# Sheet4.net
KiCad netlist of a schematic drawn in Altium Designer
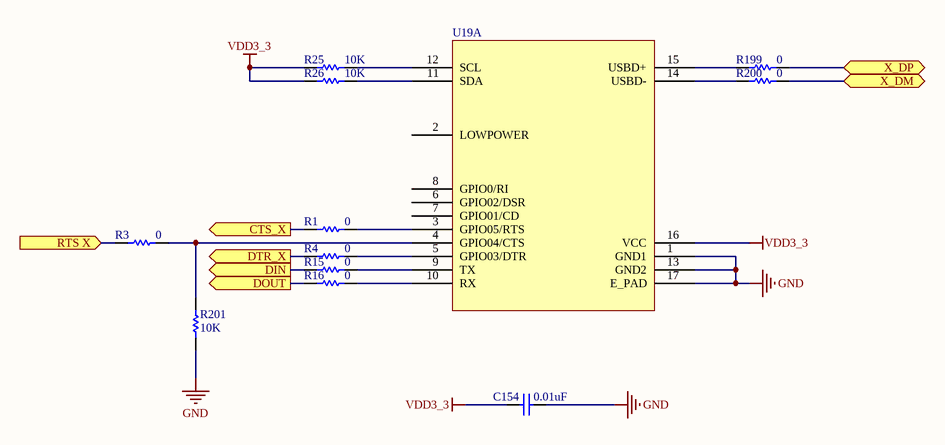
[diagram p0: Sheet4.SchDoc]

(export (version "E")
  (design (tool "Eeschema 10.0.6"))
  (components
    (comp (ref "C154")
      (value "0.01uF")
      (footprint "CAPC1005X35N")
      (description "Capacitor")
      (fields (field (name "Comment") "Cap") (field (name "PUBLISHER") "Altium Limited"))
      (libsource (lib "Miscellaneous Devices") (part "Cap"))
    )
    (comp (ref "R1")
      (value "0")
      (footprint "RESC1005X35N")
      (description "Resistor")
      (fields (field (name "Comment") "Res1") (field (name "PUBLISHER") "Altium Limited"))
      (libsource (lib "Miscellaneous Devices") (part "Res1"))
    )
    (comp (ref "R3")
      (value "0")
      (footprint "RESC1005X35N")
      (description "Resistor")
      (fields (field (name "Comment") "Res1") (field (name "PUBLISHER") "Altium Limited"))
      (libsource (lib "Miscellaneous Devices") (part "Res1"))
    )
    (comp (ref "R4")
      (value "0")
      (footprint "RESC1005X35N")
      (description "Resistor")
      (fields (field (name "Comment") "Res1") (field (name "PUBLISHER") "Altium Limited"))
      (libsource (lib "Miscellaneous Devices") (part "Res1"))
    )
    (comp (ref "R15")
      (value "0")
      (footprint "RESC1005X35N")
      (description "Resistor")
      (fields (field (name "Comment") "Res1") (field (name "PUBLISHER") "Altium Limited"))
      (libsource (lib "Miscellaneous Devices") (part "Res1"))
    )
    (comp (ref "R16")
      (value "0")
      (footprint "RESC1005X35N")
      (description "Resistor")
      (fields (field (name "Comment") "Res1") (field (name "PUBLISHER") "Altium Limited"))
      (libsource (lib "Miscellaneous Devices") (part "Res1"))
    )
    (comp (ref "R25")
      (value "10K")
      (footprint "RESC1005X35N")
      (description "Resistor")
      (fields (field (name "Comment") "Res1") (field (name "PUBLISHER") "Altium Limited"))
      (libsource (lib "Miscellaneous Devices") (part "Res1"))
    )
    (comp (ref "R26")
      (value "10K")
      (footprint "RESC1005X35N")
      (description "Resistor")
      (fields (field (name "Comment") "Res1") (field (name "PUBLISHER") "Altium Limited"))
      (libsource (lib "Miscellaneous Devices") (part "Res1"))
    )
    (comp (ref "R199")
      (value "0")
      (footprint "RESC1005X35N")
      (description "Resistor")
      (fields (field (name "Comment") "Res1") (field (name "PUBLISHER") "Altium Limited"))
      (libsource (lib "Miscellaneous Devices") (part "Res1"))
    )
    (comp (ref "R200")
      (value "0")
      (footprint "RESC1005X35N")
      (description "Resistor")
      (fields (field (name "Comment") "Res1") (field (name "PUBLISHER") "Altium Limited"))
      (libsource (lib "Miscellaneous Devices") (part "Res1"))
    )
    (comp (ref "R201")
      (value "10K")
      (footprint "RESC1005X35N")
      (description "Resistor")
      (fields (field (name "Comment") "Res1") (field (name "PUBLISHER") "Altium Limited"))
      (libsource (lib "Miscellaneous Devices") (part "Res1"))
    )
    (comp (ref "U19")
      (value "~")
      (footprint "QFN50P300X300X90-17N")
      (libsource (lib "Components - 07.03.22 - 14.02") (part "XR21V1410"))
    )
  )
  (nets
    (net (code "1") (name "/CTS_X") (class "Default")
      (node (ref "R1") (pin "1") (pinfunction "1_1") (pintype "passive"))
    )
    (net (code "2") (name "/DIN") (class "Default")
      (node (ref "R15") (pin "1") (pinfunction "1_1") (pintype "passive"))
    )
    (net (code "3") (name "/DOUT") (class "Default")
      (node (ref "R16") (pin "1") (pinfunction "1_1") (pintype "passive"))
    )
    (net (code "4") (name "/DTR_X") (class "Default")
      (node (ref "R4") (pin "1") (pinfunction "1_1") (pintype "passive"))
    )
    (net (code "5") (name "/RTS X") (class "Default")
      (node (ref "R3") (pin "1") (pinfunction "1_1") (pintype "passive"))
    )
    (net (code "6") (name "/X_DM") (class "Default")
      (node (ref "R200") (pin "2") (pinfunction "2_2") (pintype "passive"))
    )
    (net (code "7") (name "/X_DP") (class "Default")
      (node (ref "R199") (pin "2") (pinfunction "2_2") (pintype "passive"))
    )
    (net (code "8") (name "GND") (class "Default")
      (node (ref "C154") (pin "2") (pinfunction "2_2") (pintype "passive"))
      (node (ref "R201") (pin "1") (pinfunction "1_1") (pintype "passive"))
      (node (ref "U19") (pin "1") (pinfunction "GND1_1") (pintype "passive"))
      (node (ref "U19") (pin "13") (pinfunction "GND2_13") (pintype "passive"))
      (node (ref "U19") (pin "17") (pinfunction "E_PAD_17") (pintype "passive"))
    )
    (net (code "9") (name "Net-(U19A-GPIO03{slash}DTR)") (class "Default")
      (node (ref "R4") (pin "2") (pinfunction "2_2") (pintype "passive"))
      (node (ref "U19") (pin "5") (pinfunction "GPIO03/DTR_5") (pintype "passive"))
    )
    (net (code "10") (name "Net-(U19A-GPIO04{slash}CTS)") (class "Default")
      (node (ref "R201") (pin "2") (pinfunction "2_2") (pintype "passive"))
      (node (ref "R3") (pin "2") (pinfunction "2_2") (pintype "passive"))
      (node (ref "U19") (pin "4") (pinfunction "GPIO04/CTS_4") (pintype "passive"))
    )
    (net (code "11") (name "Net-(U19A-GPIO05{slash}RTS)") (class "Default")
      (node (ref "R1") (pin "2") (pinfunction "2_2") (pintype "passive"))
      (node (ref "U19") (pin "3") (pinfunction "GPIO05/RTS_3") (pintype "passive"))
    )
    (net (code "12") (name "Net-(U19A-RX)") (class "Default")
      (node (ref "R16") (pin "2") (pinfunction "2_2") (pintype "passive"))
      (node (ref "U19") (pin "10") (pinfunction "RX_10") (pintype "passive"))
    )
    (net (code "13") (name "Net-(U19A-SCL)") (class "Default")
      (node (ref "R25") (pin "2") (pinfunction "2_2") (pintype "passive"))
      (node (ref "U19") (pin "12") (pinfunction "SCL_12") (pintype "passive"))
    )
    (net (code "14") (name "Net-(U19A-SDA)") (class "Default")
      (node (ref "R26") (pin "2") (pinfunction "2_2") (pintype "passive"))
      (node (ref "U19") (pin "11") (pinfunction "SDA_11") (pintype "passive"))
    )
    (net (code "15") (name "Net-(U19A-TX)") (class "Default")
      (node (ref "R15") (pin "2") (pinfunction "2_2") (pintype "passive"))
      (node (ref "U19") (pin "9") (pinfunction "TX_9") (pintype "passive"))
    )
    (net (code "16") (name "Net-(U19A-USBD+)") (class "Default")
      (node (ref "R199") (pin "1") (pinfunction "1_1") (pintype "passive"))
      (node (ref "U19") (pin "15") (pinfunction "USBD+_15") (pintype "passive"))
    )
    (net (code "17") (name "Net-(U19A-USBD-)") (class "Default")
      (node (ref "R200") (pin "1") (pinfunction "1_1") (pintype "passive"))
      (node (ref "U19") (pin "14") (pinfunction "USBD-_14") (pintype "passive"))
    )
    (net (code "18") (name "VDD3_3") (class "Default")
      (node (ref "C154") (pin "1") (pinfunction "1_1") (pintype "passive"))
      (node (ref "R25") (pin "1") (pinfunction "1_1") (pintype "passive"))
      (node (ref "R26") (pin "1") (pinfunction "1_1") (pintype "passive"))
      (node (ref "U19") (pin "16") (pinfunction "VCC_16") (pintype "passive"))
    )
    (net (code "19") (name "unconnected-(U19A-GPIO0{slash}RI-Pad8)") (class "Default")
      (node (ref "U19") (pin "8") (pinfunction "GPIO0/RI_8") (pintype "passive"))
    )
    (net (code "20") (name "unconnected-(U19A-GPIO01{slash}CD-Pad7)") (class "Default")
      (node (ref "U19") (pin "7") (pinfunction "GPIO01/CD_7") (pintype "passive"))
    )
    (net (code "21") (name "unconnected-(U19A-GPIO02{slash}DSR-Pad6)") (class "Default")
      (node (ref "U19") (pin "6") (pinfunction "GPIO02/DSR_6") (pintype "passive"))
    )
    (net (code "22") (name "unconnected-(U19A-LOWPOWER-Pad2)") (class "Default")
      (node (ref "U19") (pin "2") (pinfunction "LOWPOWER_2") (pintype "passive"))
    )
  )
)
